# ice40_MotherBoard.net
KiCad netlist of a schematic drawn in Altium Designer
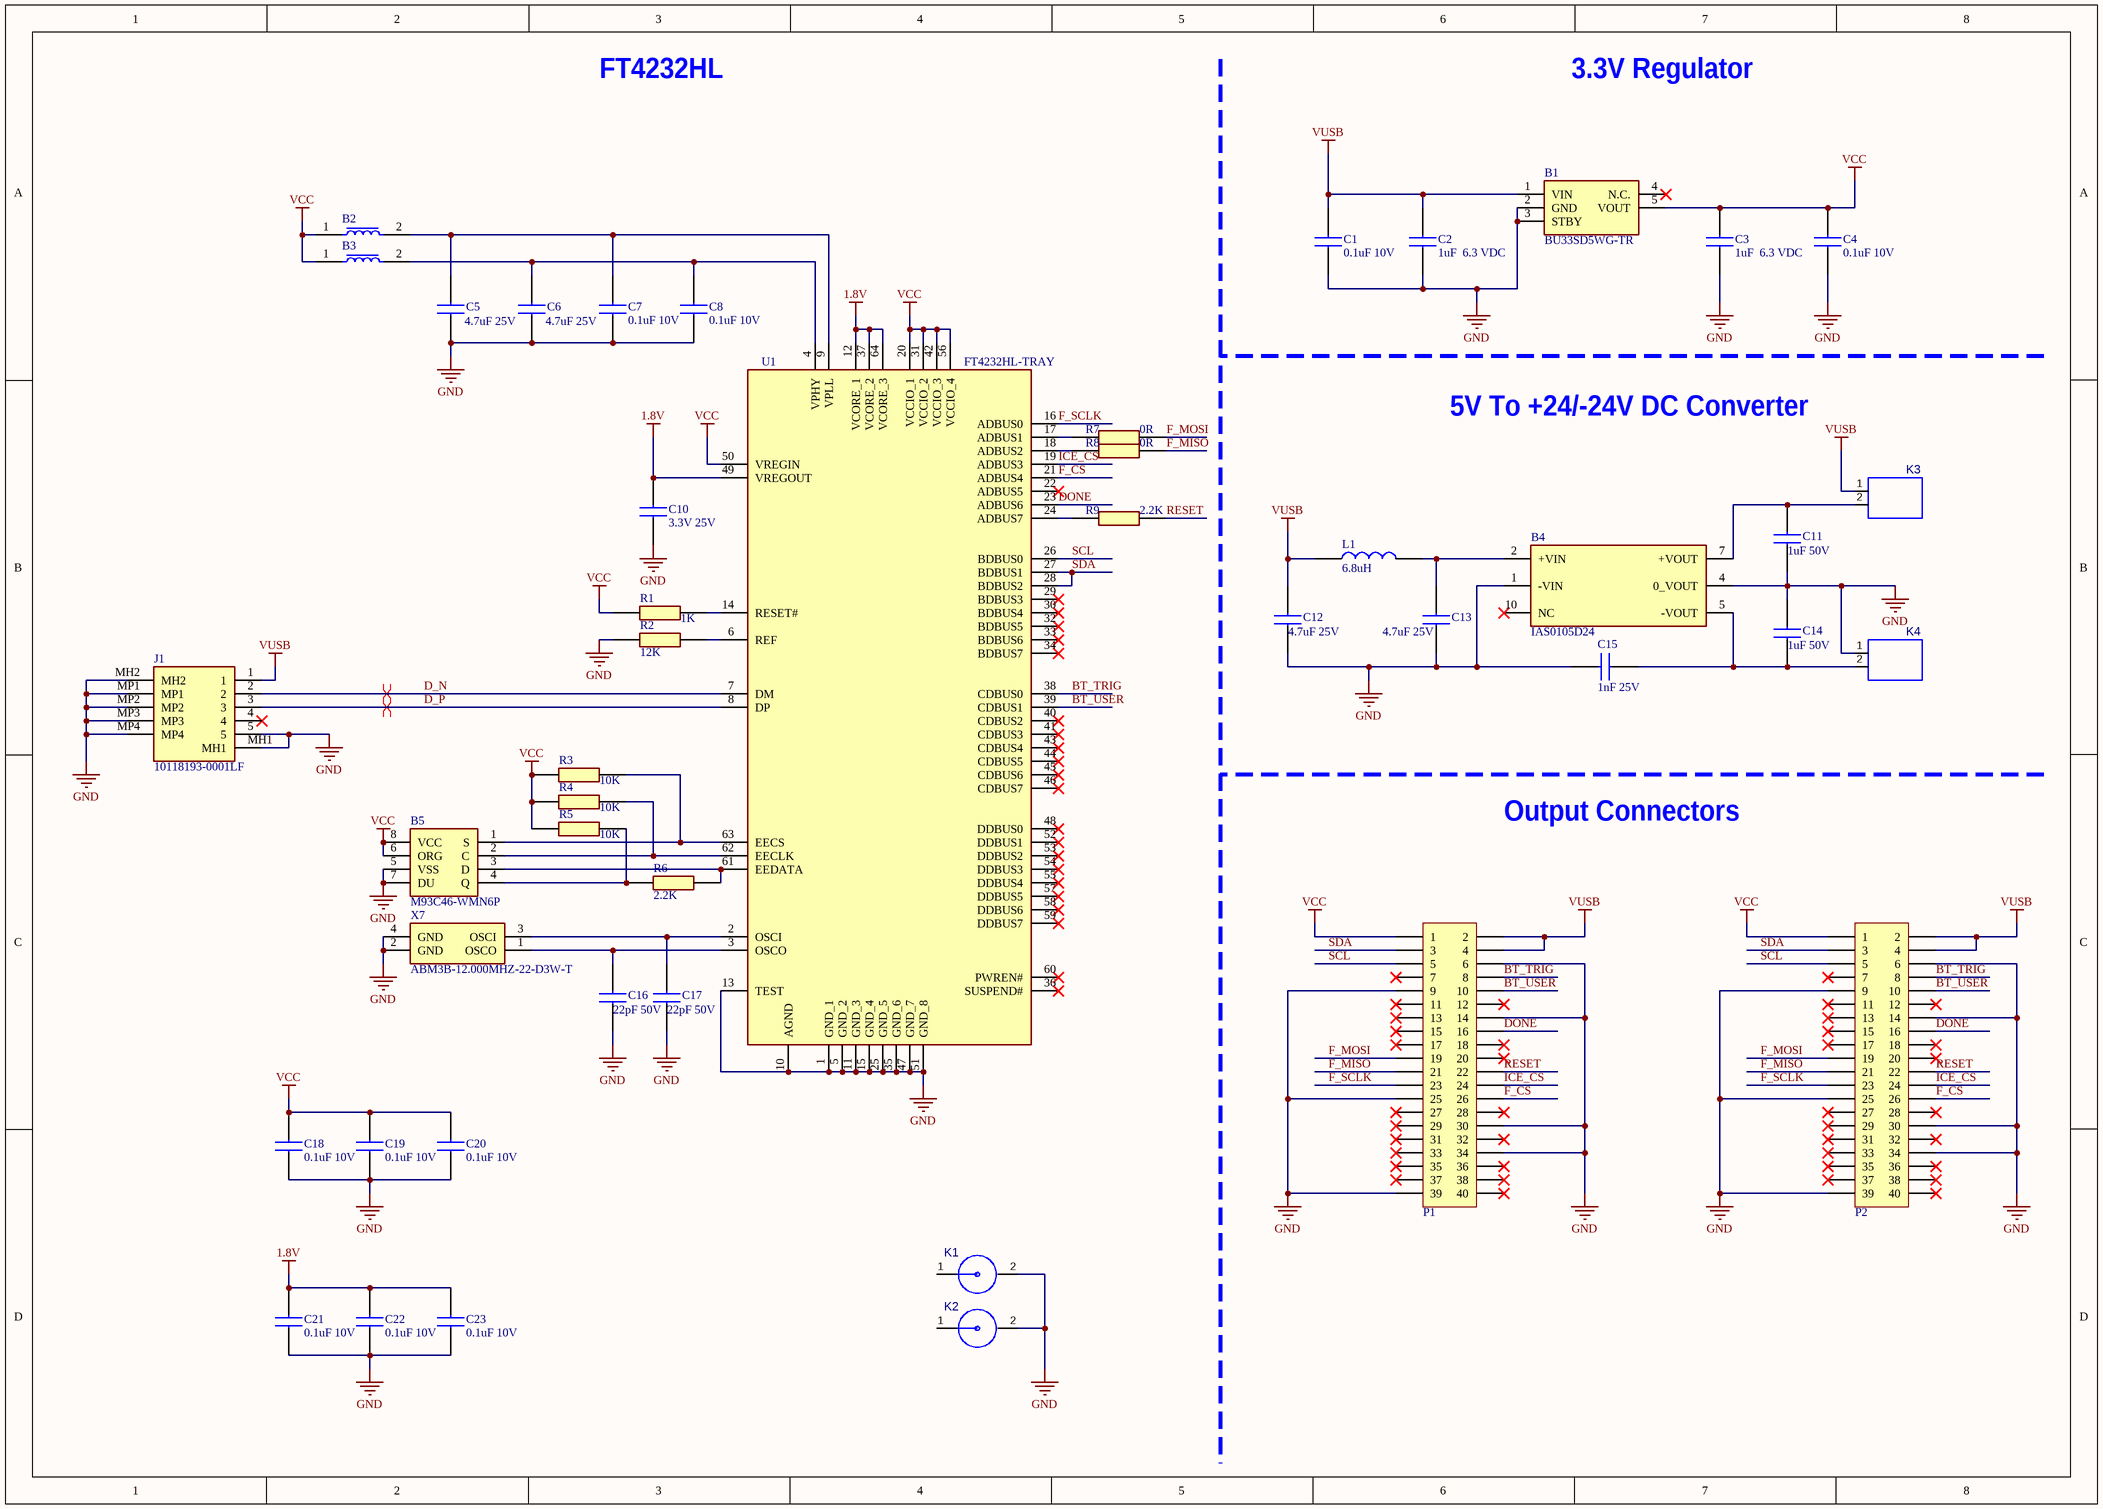
[diagram p0: ice40_MotherBoard.SchDoc]

(export (version "E")
  (design (tool "Eeschema 10.0.6"))
  (components
    (comp (ref "B1")
      (value "BU33SD5WG-TR")
      (footprint "SOT95P280X125-5N_")
      (fields (field (name "MOUSER PART NUMBER") "755-BU33SD5WG-TR"))
      (libsource (lib "BU33SD5WG-TR") (part "BU33SD5WG-TR"))
    )
    (comp (ref "B2")
      (value "BLM21AG102SN1D")
      (footprint "BLM21AG102BH1J")
      (description "BLM21_N1D Series EMI Suppression Filter 1000+/-25% at 100MHz 600mA @85")
      (fields (field (name "MOUSER PART NUMBER") "81-BLM21AG102SN1"))
      (libsource (lib "BLM21AG102SN1D") (part "BLM21AG102SN1D"))
    )
    (comp (ref "B3")
      (value "BLM21AG102SN1D")
      (footprint "BLM21AG102BH1J")
      (description "BLM21_N1D Series EMI Suppression Filter 1000+/-25% at 100MHz 600mA @85")
      (fields (field (name "MOUSER PART NUMBER") "81-BLM21AG102SN1"))
      (libsource (lib "BLM21AG102SN1D") (part "BLM21AG102SN1D"))
    )
    (comp (ref "B4")
      (value "IAS0105D24")
      (footprint "IAS0105D15_")
      (description "Isolated DC/DC Converters DC-DC, 1W, UNREGULATED, DUAL OUTPUT, SMD")
      (fields
        (field (name "MANUFACTURER_PART_NUMBER") "IAS0105D15")
        (field (name "MOUSER PART NUMBER") "209-IAS0105D15")
      )
      (libsource (lib "IAS0105D15") (part "IAS0105D15"))
    )
    (comp (ref "B5")
      (value "M93C46-WMN6P")
      (footprint "SOIC127P600X175-8N")
      (description "M93C46-WMN6P, Serial EEPROM Memory 1kbit, Serial-Microwire, 200ns 2.5  5.5 V, 8-Pin")
      (fields (field (name "MOUSER PART NUMBER") "511-M93C46-WMN6P"))
      (libsource (lib "M93C46-WMN6P") (part "M93C46-WMN6P"))
    )
    (comp (ref "C1")
      (value "0.1uF 10V")
      (footprint "C0805")
      (fields
        (field (name "MANUFACTURER_PART_NUMBER") "C0805C104K8RACAUTO")
        (field (name "MOUSER PART NUMBER") "80-C0805C104K8RAUTO")
      )
      (libsource (lib "C0805C104K8RACAUTO") (part "C0805C104K8RACAUTO"))
    )
    (comp (ref "C2")
      (value "1uF  6.3 VDC")
      (footprint "C0805")
      (fields
        (field (name "MANUFACTURER_PART_NUMBER") "C0805C105K9RACTU")
        (field (name "MOUSER PART NUMBER") "80-C0805C105K9R")
      )
      (libsource (lib "C0805C105K9RACTU") (part "C0805C105K9RACTU"))
    )
    (comp (ref "C3")
      (value "1uF  6.3 VDC")
      (footprint "C0805")
      (fields
        (field (name "MANUFACTURER_PART_NUMBER") "C0805C105K9RACTU")
        (field (name "MOUSER PART NUMBER") "80-C0805C105K9R")
      )
      (libsource (lib "C0805C105K9RACTU") (part "C0805C105K9RACTU"))
    )
    (comp (ref "C4")
      (value "0.1uF 10V")
      (footprint "C0805")
      (fields
        (field (name "MANUFACTURER_PART_NUMBER") "C0805C104K8RACAUTO")
        (field (name "MOUSER PART NUMBER") "80-C0805C104K8RAUTO")
      )
      (libsource (lib "C0805C104K8RACAUTO") (part "C0805C104K8RACAUTO"))
    )
    (comp (ref "C5")
      (value "4.7uF 25V")
      (footprint "C0805")
      (fields
        (field (name "MANUFACTURER_PART_NUMBER") "C0805C475K3RACTU")
        (field (name "MOUSER PART NUMBER") "80-C0805C475K3RACTU")
      )
      (libsource (lib "C0805C475K3RACTU") (part "C0805C475K3RACTU"))
    )
    (comp (ref "C6")
      (value "4.7uF 25V")
      (footprint "C0805")
      (fields
        (field (name "MANUFACTURER_PART_NUMBER") "C0805C475K3RACTU")
        (field (name "MOUSER PART NUMBER") "80-C0805C475K3RACTU")
      )
      (libsource (lib "C0805C475K3RACTU") (part "C0805C475K3RACTU"))
    )
    (comp (ref "C7")
      (value "0.1uF 10V")
      (footprint "C0805")
      (fields
        (field (name "MANUFACTURER_PART_NUMBER") "C0805C104K8RACAUTO")
        (field (name "MOUSER PART NUMBER") "80-C0805C104K8RAUTO")
      )
      (libsource (lib "C0805C104K8RACAUTO") (part "C0805C104K8RACAUTO"))
    )
    (comp (ref "C8")
      (value "0.1uF 10V")
      (footprint "C0805")
      (fields
        (field (name "MANUFACTURER_PART_NUMBER") "C0805C104K8RACAUTO")
        (field (name "MOUSER PART NUMBER") "80-C0805C104K8RAUTO")
      )
      (libsource (lib "C0805C104K8RACAUTO") (part "C0805C104K8RACAUTO"))
    )
    (comp (ref "C10")
      (value "3.3V 25V")
      (footprint "C0805")
      (description "TDK 0805 C 3.3uF Ceramic Multilayer Capacitor, 25 V dc, +125C, X7R Dielectric, +/-10%")
      (fields
        (field (name "MANUFACTURER_PART_NUMBER") "C2012X7R1E335K125AB")
        (field (name "MOUSER PART NUMBER") "810-C2012X7R1E335K")
      )
      (libsource (lib "C2012X7R1E335K125AB") (part "C2012X7R1E335K125AB"))
    )
    (comp (ref "C11")
      (value "1uF 50V")
      (footprint "C0805")
      (fields
        (field (name "MANUFACTURER_PART_NUMBER") "C0805C105K5RACTU")
        (field (name "MOUSER PART NUMBER") "80-C0805C105K5R")
      )
      (libsource (lib "C0805C105K5RACTU") (part "C0805C105K5RACTU"))
    )
    (comp (ref "C12")
      (value "4.7uF 25V")
      (footprint "C0805")
      (fields
        (field (name "MANUFACTURER_PART_NUMBER") "C0805C475K3RACTU")
        (field (name "MOUSER PART NUMBER") "80-C0805C475K3RACTU")
      )
      (libsource (lib "C0805C475K3RACTU") (part "C0805C475K3RACTU"))
    )
    (comp (ref "C13")
      (value "4.7uF 25V")
      (footprint "C0805")
      (fields
        (field (name "MANUFACTURER_PART_NUMBER") "C0805C475K3RACTU")
        (field (name "MOUSER PART NUMBER") "80-C0805C475K3RACTU")
      )
      (libsource (lib "C0805C475K3RACTU") (part "C0805C475K3RACTU"))
    )
    (comp (ref "C14")
      (value "1uF 50V")
      (footprint "C0805")
      (fields
        (field (name "MANUFACTURER_PART_NUMBER") "C0805C105K5RACTU")
        (field (name "MOUSER PART NUMBER") "80-C0805C105K5R")
      )
      (libsource (lib "C0805C105K5RACTU") (part "C0805C105K5RACTU"))
    )
    (comp (ref "C15")
      (value "1nF 25V")
      (footprint "C0805")
      (fields
        (field (name "MANUFACTURER_PART_NUMBER") "C0805C102K8RACTU")
        (field (name "MOUSER PART NUMBER") "80-C0805C102K8R")
      )
      (libsource (lib "C0805C102K8RACTU") (part "C0805C102K8RACTU"))
    )
    (comp (ref "C16")
      (value "22pF 50V")
      (footprint "C0805")
      (fields
        (field (name "MANUFACTURER_PART_NUMBER") "C0805C220F5GACTU")
        (field (name "MOUSER PART NUMBER") "80-C0805C220F5G")
      )
      (libsource (lib "C0805C220F5GACTU") (part "C0805C220F5GACTU"))
    )
    (comp (ref "C17")
      (value "22pF 50V")
      (footprint "C0805")
      (fields
        (field (name "MANUFACTURER_PART_NUMBER") "C0805C220F5GACTU")
        (field (name "MOUSER PART NUMBER") "80-C0805C220F5G")
      )
      (libsource (lib "C0805C220F5GACTU") (part "C0805C220F5GACTU"))
    )
    (comp (ref "C18")
      (value "0.1uF 10V")
      (footprint "C0805")
      (fields
        (field (name "MANUFACTURER_PART_NUMBER") "C0805C104K8RACAUTO")
        (field (name "MOUSER PART NUMBER") "80-C0805C104K8RAUTO")
      )
      (libsource (lib "C0805C104K8RACAUTO") (part "C0805C104K8RACAUTO"))
    )
    (comp (ref "C19")
      (value "0.1uF 10V")
      (footprint "C0805")
      (fields
        (field (name "MANUFACTURER_PART_NUMBER") "C0805C104K8RACAUTO")
        (field (name "MOUSER PART NUMBER") "80-C0805C104K8RAUTO")
      )
      (libsource (lib "C0805C104K8RACAUTO") (part "C0805C104K8RACAUTO"))
    )
    (comp (ref "C20")
      (value "0.1uF 10V")
      (footprint "C0805")
      (fields
        (field (name "MANUFACTURER_PART_NUMBER") "C0805C104K8RACAUTO")
        (field (name "MOUSER PART NUMBER") "80-C0805C104K8RAUTO")
      )
      (libsource (lib "C0805C104K8RACAUTO") (part "C0805C104K8RACAUTO"))
    )
    (comp (ref "C21")
      (value "0.1uF 10V")
      (footprint "C0805")
      (fields
        (field (name "MANUFACTURER_PART_NUMBER") "C0805C104K8RACAUTO")
        (field (name "MOUSER PART NUMBER") "80-C0805C104K8RAUTO")
      )
      (libsource (lib "C0805C104K8RACAUTO") (part "C0805C104K8RACAUTO"))
    )
    (comp (ref "C22")
      (value "0.1uF 10V")
      (footprint "C0805")
      (fields
        (field (name "MANUFACTURER_PART_NUMBER") "C0805C104K8RACAUTO")
        (field (name "MOUSER PART NUMBER") "80-C0805C104K8RAUTO")
      )
      (libsource (lib "C0805C104K8RACAUTO") (part "C0805C104K8RACAUTO"))
    )
    (comp (ref "C23")
      (value "0.1uF 10V")
      (footprint "C0805")
      (fields
        (field (name "MANUFACTURER_PART_NUMBER") "C0805C104K8RACAUTO")
        (field (name "MOUSER PART NUMBER") "80-C0805C104K8RAUTO")
      )
      (libsource (lib "C0805C104K8RACAUTO") (part "C0805C104K8RACAUTO"))
    )
    (comp (ref "J1")
      (value "10118193-0001LF")
      (footprint "shunt_resistor:101181930001LF")
      (description "Connector")
      (fields (field (name "MOUSER PART NUMBER") "649-10118193-0001LF"))
      (libsource (lib "*") (part "10118193-0001LF"))
    )
    (comp (ref "K1")
      (value "SMA_Edge")
      (footprint "AMPHENOL_132357-11_")
      (libsource (lib "alt_vovan") (part "SMA_Edge"))
    )
    (comp (ref "K2")
      (value "SMA_Edge")
      (footprint "AMPHENOL_132357-11_")
      (libsource (lib "alt_vovan") (part "SMA_Edge"))
    )
    (comp (ref "K3") (value "1x2PLS") (footprint "55342061_") (libsource (lib "alt2017") (part "1x2PLS")))
    (comp (ref "K4") (value "1x2PLS") (footprint "55342061_") (libsource (lib "alt2017") (part "1x2PLS")))
    (comp (ref "L1")
      (value "6.8uH")
      (footprint "INDC2012X110N_")
      (description "Fixed Inductors 0805 6.8uH 600mA DCR=420mOhms RF")
      (fields
        (field (name "MANUFACTURER_PART_NUMBER") "PE-0805CLH6R8STS")
        (field (name "MOUSER PART NUMBER") "673-PE-0805CLH6R8STS")
      )
      (libsource (lib "INDC2012X110N") (part "PE-0805CLH6R8STS"))
    )
    (comp (ref "P1")
      (value "2x20 2.54mm vertical")
      (footprint "RHDR40W97P254X254_2X20_5130X508X860P_")
      (description "SSQ-110-02-G-D-RA")
      (fields (field (name "PUBLISHER") "Altium Limited"))
      (libsource (lib "alt2017") (part "2x20 2.54mm vertical"))
    )
    (comp (ref "P2")
      (value "2x20 2.54mm vertical")
      (footprint "RHDR40W97P254X254_2X20_5130X508X860P_")
      (description "SSQ-110-02-G-D-RA")
      (fields (field (name "PUBLISHER") "Altium Limited"))
      (libsource (lib "alt2017") (part "2x20 2.54mm vertical"))
    )
    (comp (ref "R1")
      (value "1K")
      (footprint "6-0805_M")
      (description "RESISTOR, 0805 1K Ohm +/-5% 0.125 W")
      (fields
        (field (name "MANUFACTURER_PART_NUMBER") "ERJ-6GEYJ102V")
        (field (name "MOUSER PART NUMBER") "667-ERJ-6GEYJ102V")
      )
      (libsource (lib "ERJ-6GEYJ102V") (part "ERJ-6GEYJ102V"))
    )
    (comp (ref "R2")
      (value "12K")
      (footprint "6-0805_M")
      (description "Thick Film Resistors - SMD 0805 12Kohms 0.5W 1% AEC-Q200")
      (fields
        (field (name "MANUFACTURER_PART_NUMBER") "ERJ-P06F1202V")
        (field (name "MOUSER PART NUMBER") "667-ERJ-P06F1202V")
      )
      (libsource (lib "ERJ-P06F1202V") (part "ERJ-P06F1202V"))
    )
    (comp (ref "R3")
      (value "10K")
      (footprint "6-0805_M")
      (description "Resistor - SMD 10 kOhms 0805")
      (fields
        (field (name "MANUFACTURER_PART_NUMBER") "RC0805DR-072K2L")
        (field (name "MOUSER PART NUMBER") "603-RC0805DR-072K2L")
      )
      (libsource (lib "RC0805DR-072K2L") (part "RC0805DR-072K2L"))
    )
    (comp (ref "R4")
      (value "10K")
      (footprint "6-0805_M")
      (description "Resistor - SMD 10 kOhms 0805")
      (fields
        (field (name "MANUFACTURER_PART_NUMBER") "RC0805DR-072K2L")
        (field (name "MOUSER PART NUMBER") "603-RC0805DR-072K2L")
      )
      (libsource (lib "") (part "RC0805DR-072K2L_1"))
    )
    (comp (ref "R5")
      (value "10K")
      (footprint "6-0805_M")
      (description "Resistor - SMD 10 kOhms 0805")
      (fields
        (field (name "MANUFACTURER_PART_NUMBER") "RC0805DR-072K2L")
        (field (name "MOUSER PART NUMBER") "603-RC0805DR-072K2L")
      )
      (libsource (lib "") (part "RC0805DR-072K2L_1"))
    )
    (comp (ref "R6")
      (value "2.2K")
      (footprint "6-0805_M")
      (description "Thick Film Resistors - SMD 2.2 kOhms 125 mW 0805 1%")
      (fields
        (field (name "MANUFACTURER_PART_NUMBER") "ERJ-P06F1202V")
        (field (name "MOUSER PART NUMBER") "667-ERJ-P06F1202V")
      )
      (libsource (lib "ERJ-P06F1202V") (part "ERJ-P06F1202V"))
    )
    (comp (ref "R7")
      (value "0R")
      (footprint "0603-R")
      (description "RESISTOR, 0805 0R")
      (fields
        (field (name "MANUFACTURER_PART_NUMBER") "ERJ-6GEYJ102V")
        (field (name "MOUSER PART NUMBER") "667-ERJ-6GEYJ102V")
      )
      (libsource (lib "ERJ-6GEYJ102V") (part "ERJ-6GEYJ102V"))
    )
    (comp (ref "R8")
      (value "0R")
      (footprint "0603-R")
      (description "RESISTOR, 0805 0R")
      (fields
        (field (name "MANUFACTURER_PART_NUMBER") "ERJ-6GEYJ102V")
        (field (name "MOUSER PART NUMBER") "667-ERJ-6GEYJ102V")
      )
      (libsource (lib "ERJ-6GEYJ102V") (part "ERJ-6GEYJ102V"))
    )
    (comp (ref "R9")
      (value "2.2K")
      (footprint "6-0805_M")
      (description "Thick Film Resistors - SMD 2.2 kOhms 125 mW 0805 1%")
      (fields
        (field (name "MANUFACTURER_PART_NUMBER") "ERJ-P06F1202V")
        (field (name "MOUSER PART NUMBER") "667-ERJ-P06F1202V")
      )
      (libsource (lib "ERJ-P06F1202V") (part "ERJ-P06F1202V"))
    )
    (comp (ref "U1")
      (value "FT4232HL-TRAY")
      (footprint "QFP50P1200X1200X160-64N")
      (description "IC USB HS QUAD UART/SYNC 64-LQFP")
      (fields (field (name "MOUSER PART NUMBER") "895-FT4232HL-TRAY"))
      (libsource (lib "FT4232HL-TRAY") (part "FT4232HL-TRAY"))
    )
    (comp (ref "X7")
      (value "ABM3B-12.000MHZ-22-D3W-T")
      (footprint "ABM3B")
      (description "Crystals 12MHz 22pF 25ppm -40C +85C")
      (fields (field (name "MOUSER PART NUMBER") "815-ABM3B-12-22-D3WT"))
      (libsource (lib "ABM3B-12.000MHZ-22-D3W-T") (part "ABM3B-12.000MHZ-22-D3W-T"))
    )
  )
  (nets
    (net (code "1") (name "/BT_TRIG") (class "Default")
      (node (ref "P1") (pin "8") (pinfunction "8_8") (pintype "passive"))
      (node (ref "P2") (pin "8") (pinfunction "8_8") (pintype "passive"))
      (node (ref "U1") (pin "38") (pinfunction "CDBUS0_38") (pintype "passive"))
    )
    (net (code "2") (name "/BT_USER") (class "Default")
      (node (ref "P1") (pin "10") (pinfunction "10_10") (pintype "passive"))
      (node (ref "P2") (pin "10") (pinfunction "10_10") (pintype "passive"))
      (node (ref "U1") (pin "39") (pinfunction "CDBUS1_39") (pintype "passive"))
    )
    (net (code "3") (name "/DONE") (class "Default")
      (node (ref "P1") (pin "16") (pinfunction "16_16") (pintype "passive"))
      (node (ref "P2") (pin "16") (pinfunction "16_16") (pintype "passive"))
      (node (ref "U1") (pin "23") (pinfunction "ADBUS6_23") (pintype "passive"))
    )
    (net (code "4") (name "/D_N") (class "Default")
      (node (ref "J1") (pin "2") (pinfunction "2_2") (pintype "passive"))
      (node (ref "U1") (pin "7") (pinfunction "DM_7") (pintype "passive"))
    )
    (net (code "5") (name "/D_P") (class "Default")
      (node (ref "J1") (pin "3") (pinfunction "3_3") (pintype "passive"))
      (node (ref "U1") (pin "8") (pinfunction "DP_8") (pintype "passive"))
    )
    (net (code "6") (name "/F_CS") (class "Default")
      (node (ref "P1") (pin "26") (pinfunction "26_26") (pintype "passive"))
      (node (ref "P2") (pin "26") (pinfunction "26_26") (pintype "passive"))
      (node (ref "U1") (pin "21") (pinfunction "ADBUS4_21") (pintype "passive"))
    )
    (net (code "7") (name "/F_MISO") (class "Default")
      (node (ref "P1") (pin "21") (pinfunction "21_21") (pintype "passive"))
      (node (ref "P2") (pin "21") (pinfunction "21_21") (pintype "passive"))
      (node (ref "R8") (pin "2") (pinfunction "R2_2") (pintype "passive"))
    )
    (net (code "8") (name "/F_MOSI") (class "Default")
      (node (ref "P1") (pin "19") (pinfunction "19_19") (pintype "passive"))
      (node (ref "P2") (pin "19") (pinfunction "19_19") (pintype "passive"))
      (node (ref "R7") (pin "2") (pinfunction "R2_2") (pintype "passive"))
    )
    (net (code "9") (name "/F_SCLK") (class "Default")
      (node (ref "P1") (pin "23") (pinfunction "23_23") (pintype "passive"))
      (node (ref "P2") (pin "23") (pinfunction "23_23") (pintype "passive"))
      (node (ref "U1") (pin "16") (pinfunction "ADBUS0_16") (pintype "passive"))
    )
    (net (code "10") (name "/ICE_CS") (class "Default")
      (node (ref "P1") (pin "24") (pinfunction "24_24") (pintype "passive"))
      (node (ref "P2") (pin "24") (pinfunction "24_24") (pintype "passive"))
      (node (ref "U1") (pin "19") (pinfunction "ADBUS3_19") (pintype "passive"))
    )
    (net (code "11") (name "/RESET") (class "Default")
      (node (ref "P1") (pin "22") (pinfunction "22_22") (pintype "passive"))
      (node (ref "P2") (pin "22") (pinfunction "22_22") (pintype "passive"))
      (node (ref "R9") (pin "2") (pinfunction "2_2") (pintype "passive"))
    )
    (net (code "12") (name "/SCL") (class "Default")
      (node (ref "P1") (pin "5") (pinfunction "5_5") (pintype "passive"))
      (node (ref "P2") (pin "5") (pinfunction "5_5") (pintype "passive"))
      (node (ref "U1") (pin "26") (pinfunction "BDBUS0_26") (pintype "passive"))
    )
    (net (code "13") (name "/SDA") (class "Default")
      (node (ref "P1") (pin "3") (pinfunction "3_3") (pintype "passive"))
      (node (ref "P2") (pin "3") (pinfunction "3_3") (pintype "passive"))
      (node (ref "U1") (pin "27") (pinfunction "BDBUS1_27") (pintype "passive"))
      (node (ref "U1") (pin "28") (pinfunction "BDBUS2_28") (pintype "passive"))
    )
    (net (code "14") (name "1.8V") (class "Default")
      (node (ref "C10") (pin "2") (pinfunction "2_2") (pintype "passive"))
      (node (ref "C21") (pin "2") (pinfunction "2_2") (pintype "passive"))
      (node (ref "C22") (pin "2") (pinfunction "2_2") (pintype "passive"))
      (node (ref "C23") (pin "2") (pinfunction "2_2") (pintype "passive"))
      (node (ref "U1") (pin "12") (pinfunction "VCORE_1_12") (pintype "passive"))
      (node (ref "U1") (pin "37") (pinfunction "VCORE_2_37") (pintype "passive"))
      (node (ref "U1") (pin "49") (pinfunction "VREGOUT_49") (pintype "passive"))
      (node (ref "U1") (pin "64") (pinfunction "VCORE_3_64") (pintype "passive"))
    )
    (net (code "15") (name "GND") (class "Default")
      (node (ref "B1") (pin "2") (pinfunction "GND_2") (pintype "passive"))
      (node (ref "B1") (pin "3") (pinfunction "STBY_3") (pintype "passive"))
      (node (ref "B4") (pin "1") (pinfunction "-VIN_1") (pintype "passive"))
      (node (ref "B4") (pin "4") (pinfunction "0_VOUT_4") (pintype "passive"))
      (node (ref "B5") (pin "5") (pinfunction "VSS_5") (pintype "power_in"))
      (node (ref "B5") (pin "7") (pinfunction "DU_7") (pintype "passive"))
      (node (ref "C1") (pin "1") (pinfunction "1_1") (pintype "passive"))
      (node (ref "C10") (pin "1") (pinfunction "1_1") (pintype "passive"))
      (node (ref "C11") (pin "1") (pinfunction "1_1") (pintype "passive"))
      (node (ref "C12") (pin "1") (pinfunction "1_1") (pintype "passive"))
      (node (ref "C13") (pin "1") (pinfunction "1_1") (pintype "passive"))
      (node (ref "C14") (pin "2") (pinfunction "2_2") (pintype "passive"))
      (node (ref "C15") (pin "1") (pinfunction "1_1") (pintype "passive"))
      (node (ref "C16") (pin "1") (pinfunction "1_1") (pintype "passive"))
      (node (ref "C17") (pin "1") (pinfunction "1_1") (pintype "passive"))
      (node (ref "C18") (pin "1") (pinfunction "1_1") (pintype "passive"))
      (node (ref "C19") (pin "1") (pinfunction "1_1") (pintype "passive"))
      (node (ref "C2") (pin "1") (pinfunction "1_1") (pintype "passive"))
      (node (ref "C20") (pin "1") (pinfunction "1_1") (pintype "passive"))
      (node (ref "C21") (pin "1") (pinfunction "1_1") (pintype "passive"))
      (node (ref "C22") (pin "1") (pinfunction "1_1") (pintype "passive"))
      (node (ref "C23") (pin "1") (pinfunction "1_1") (pintype "passive"))
      (node (ref "C3") (pin "1") (pinfunction "1_1") (pintype "passive"))
      (node (ref "C4") (pin "1") (pinfunction "1_1") (pintype "passive"))
      (node (ref "C5") (pin "1") (pinfunction "1_1") (pintype "passive"))
      (node (ref "C6") (pin "1") (pinfunction "1_1") (pintype "passive"))
      (node (ref "C7") (pin "1") (pinfunction "1_1") (pintype "passive"))
      (node (ref "C8") (pin "1") (pinfunction "1_1") (pintype "passive"))
      (node (ref "J1") (pin "5") (pinfunction "5_5") (pintype "passive"))
      (node (ref "J1") (pin "MH1") (pinfunction "MH1_MH1") (pintype "passive"))
      (node (ref "J1") (pin "MH2") (pinfunction "MH2_MH2") (pintype "passive"))
      (node (ref "J1") (pin "MP1") (pinfunction "MP1_MP1") (pintype "passive"))
      (node (ref "J1") (pin "MP2") (pinfunction "MP2_MP2") (pintype "passive"))
      (node (ref "J1") (pin "MP3") (pinfunction "MP3_MP3") (pintype "passive"))
      (node (ref "J1") (pin "MP4") (pinfunction "MP4_MP4") (pintype "passive"))
      (node (ref "K1") (pin "2") (pinfunction "2_2") (pintype "passive"))
      (node (ref "K2") (pin "2") (pinfunction "2_2") (pintype "passive"))
      (node (ref "K4") (pin "1") (pinfunction "1_1") (pintype "passive"))
      (node (ref "P1") (pin "14") (pinfunction "14_14") (pintype "passive"))
      (node (ref "P1") (pin "25") (pinfunction "25_25") (pintype "passive"))
      (node (ref "P1") (pin "30") (pinfunction "30_30") (pintype "passive"))
      (node (ref "P1") (pin "34") (pinfunction "34_34") (pintype "passive"))
      (node (ref "P1") (pin "39") (pinfunction "39_39") (pintype "passive"))
      (node (ref "P1") (pin "6") (pinfunction "6_6") (pintype "passive"))
      (node (ref "P1") (pin "9") (pinfunction "9_9") (pintype "passive"))
      (node (ref "P2") (pin "14") (pinfunction "14_14") (pintype "passive"))
      (node (ref "P2") (pin "25") (pinfunction "25_25") (pintype "passive"))
      (node (ref "P2") (pin "30") (pinfunction "30_30") (pintype "passive"))
      (node (ref "P2") (pin "34") (pinfunction "34_34") (pintype "passive"))
      (node (ref "P2") (pin "39") (pinfunction "39_39") (pintype "passive"))
      (node (ref "P2") (pin "6") (pinfunction "6_6") (pintype "passive"))
      (node (ref "P2") (pin "9") (pinfunction "9_9") (pintype "passive"))
      (node (ref "R2") (pin "1") (pinfunction "1_1") (pintype "passive"))
      (node (ref "U1") (pin "1") (pinfunction "GND_1_1") (pintype "passive"))
      (node (ref "U1") (pin "10") (pinfunction "AGND_10") (pintype "passive"))
      (node (ref "U1") (pin "11") (pinfunction "GND_3_11") (pintype "passive"))
      (node (ref "U1") (pin "13") (pinfunction "TEST_13") (pintype "passive"))
      (node (ref "U1") (pin "15") (pinfunction "GND_4_15") (pintype "passive"))
      (node (ref "U1") (pin "25") (pinfunction "GND_5_25") (pintype "passive"))
      (node (ref "U1") (pin "35") (pinfunction "GND_6_35") (pintype "passive"))
      (node (ref "U1") (pin "47") (pinfunction "GND_7_47") (pintype "passive"))
      (node (ref "U1") (pin "5") (pinfunction "GND_2_5") (pintype "passive"))
      (node (ref "U1") (pin "51") (pinfunction "GND_8_51") (pintype "passive"))
      (node (ref "X7") (pin "2") (pinfunction "GND_2") (pintype "passive"))
      (node (ref "X7") (pin "4") (pinfunction "GND_4") (pintype "passive"))
    )
    (net (code "16") (name "Net-(B4-+VIN)") (class "Default")
      (node (ref "B4") (pin "2") (pinfunction "+VIN_2") (pintype "passive"))
      (node (ref "C13") (pin "2") (pinfunction "2_2") (pintype "passive"))
      (node (ref "L1") (pin "2") (pinfunction "2_2") (pintype "passive"))
    )
    (net (code "17") (name "Net-(B4-+VOUT)") (class "Default")
      (node (ref "B4") (pin "7") (pinfunction "+VOUT_7") (pintype "passive"))
      (node (ref "C11") (pin "2") (pinfunction "2_2") (pintype "passive"))
      (node (ref "K3") (pin "2") (pinfunction "2_2") (pintype "passive"))
    )
    (net (code "18") (name "Net-(B4--VOUT)") (class "Default")
      (node (ref "B4") (pin "5") (pinfunction "-VOUT_5") (pintype "passive"))
      (node (ref "C14") (pin "1") (pinfunction "1_1") (pintype "passive"))
      (node (ref "C15") (pin "2") (pinfunction "2_2") (pintype "passive"))
      (node (ref "K4") (pin "2") (pinfunction "2_2") (pintype "passive"))
    )
    (net (code "19") (name "Net-(B5-C)") (class "Default")
      (node (ref "B5") (pin "2") (pinfunction "C_2") (pintype "passive"))
      (node (ref "R4") (pin "2") (pinfunction "2_2") (pintype "passive"))
      (node (ref "U1") (pin "62") (pinfunction "EECLK_62") (pintype "passive"))
    )
    (net (code "20") (name "Net-(B5-D)") (class "Default")
      (node (ref "B5") (pin "3") (pinfunction "D_3") (pintype "passive"))
      (node (ref "R6") (pin "2") (pinfunction "2_2") (pintype "passive"))
      (node (ref "U1") (pin "61") (pinfunction "EEDATA_61") (pintype "passive"))
    )
    (net (code "21") (name "Net-(B5-Q)") (class "Default")
      (node (ref "B5") (pin "4") (pinfunction "Q_4") (pintype "passive"))
      (node (ref "R5") (pin "2") (pinfunction "2_2") (pintype "passive"))
      (node (ref "R6") (pin "1") (pinfunction "1_1") (pintype "passive"))
    )
    (net (code "22") (name "Net-(B5-S)") (class "Default")
      (node (ref "B5") (pin "1") (pinfunction "S_1") (pintype "passive"))
      (node (ref "R3") (pin "1") (pinfunction "1_1") (pintype "passive"))
      (node (ref "U1") (pin "63") (pinfunction "EECS_63") (pintype "passive"))
    )
    (net (code "23") (name "Net-(R1-R2)") (class "Default")
      (node (ref "R1") (pin "2") (pinfunction "R2_2") (pintype "passive"))
      (node (ref "U1") (pin "14") (pinfunction "RESET#_14") (pintype "passive"))
    )
    (net (code "24") (name "Net-(R7-R1)") (class "Default")
      (node (ref "R7") (pin "1") (pinfunction "R1_1") (pintype "passive"))
      (node (ref "U1") (pin "17") (pinfunction "ADBUS1_17") (pintype "passive"))
    )
    (net (code "25") (name "Net-(R8-R1)") (class "Default")
      (node (ref "R8") (pin "1") (pinfunction "R1_1") (pintype "passive"))
      (node (ref "U1") (pin "18") (pinfunction "ADBUS2_18") (pintype "passive"))
    )
    (net (code "26") (name "Net-(U1-ADBUS7)") (class "Default")
      (node (ref "R9") (pin "1") (pinfunction "1_1") (pintype "passive"))
      (node (ref "U1") (pin "24") (pinfunction "ADBUS7_24") (pintype "passive"))
    )
    (net (code "27") (name "Net-(U1-OSCI)") (class "Default")
      (node (ref "C17") (pin "2") (pinfunction "2_2") (pintype "passive"))
      (node (ref "U1") (pin "2") (pinfunction "OSCI_2") (pintype "passive"))
      (node (ref "X7") (pin "3") (pinfunction "OSCI_3") (pintype "passive"))
    )
    (net (code "28") (name "Net-(U1-OSCO)") (class "Default")
      (node (ref "C16") (pin "2") (pinfunction "2_2") (pintype "passive"))
      (node (ref "U1") (pin "3") (pinfunction "OSCO_3") (pintype "passive"))
      (node (ref "X7") (pin "1") (pinfunction "OSCO_1") (pintype "passive"))
    )
    (net (code "29") (name "Net-(U1-REF)") (class "Default")
      (node (ref "R2") (pin "2") (pinfunction "2_2") (pintype "passive"))
      (node (ref "U1") (pin "6") (pinfunction "REF_6") (pintype "passive"))
    )
    (net (code "30") (name "Net-(U1-VPHY)") (class "Default")
      (node (ref "B3") (pin "2") (pinfunction "2_2") (pintype "passive"))
      (node (ref "C6") (pin "2") (pinfunction "2_2") (pintype "passive"))
      (node (ref "C8") (pin "2") (pinfunction "2_2") (pintype "passive"))
      (node (ref "U1") (pin "4") (pinfunction "VPHY_4") (pintype "passive"))
    )
    (net (code "31") (name "Net-(U1-VPLL)") (class "Default")
      (node (ref "B2") (pin "2") (pinfunction "2_2") (pintype "passive"))
      (node (ref "C5") (pin "2") (pinfunction "2_2") (pintype "passive"))
      (node (ref "C7") (pin "2") (pinfunction "2_2") (pintype "passive"))
      (node (ref "U1") (pin "9") (pinfunction "VPLL_9") (pintype "passive"))
    )
    (net (code "32") (name "VCC") (class "Default")
      (node (ref "B1") (pin "5") (pinfunction "VOUT_5") (pintype "passive"))
      (node (ref "B2") (pin "1") (pinfunction "1_1") (pintype "passive"))
      (node (ref "B3") (pin "1") (pinfunction "1_1") (pintype "passive"))
      (node (ref "B5") (pin "6") (pinfunction "ORG_6") (pintype "passive"))
      (node (ref "B5") (pin "8") (pinfunction "VCC_8") (pintype "power_in"))
      (node (ref "C18") (pin "2") (pinfunction "2_2") (pintype "passive"))
      (node (ref "C19") (pin "2") (pinfunction "2_2") (pintype "passive"))
      (node (ref "C20") (pin "2") (pinfunction "2_2") (pintype "passive"))
      (node (ref "C3") (pin "2") (pinfunction "2_2") (pintype "passive"))
      (node (ref "C4") (pin "2") (pinfunction "2_2") (pintype "passive"))
      (node (ref "P1") (pin "1") (pinfunction "1_1") (pintype "passive"))
      (node (ref "P2") (pin "1") (pinfunction "1_1") (pintype "passive"))
      (node (ref "R1") (pin "1") (pinfunction "R1_1") (pintype "passive"))
      (node (ref "R3") (pin "2") (pinfunction "2_2") (pintype "passive"))
      (node (ref "R4") (pin "1") (pinfunction "1_1") (pintype "passive"))
      (node (ref "R5") (pin "1") (pinfunction "1_1") (pintype "passive"))
      (node (ref "U1") (pin "20") (pinfunction "VCCIO_1_20") (pintype "passive"))
      (node (ref "U1") (pin "31") (pinfunction "VCCIO_2_31") (pintype "passive"))
      (node (ref "U1") (pin "42") (pinfunction "VCCIO_3_42") (pintype "passive"))
      (node (ref "U1") (pin "50") (pinfunction "VREGIN_50") (pintype "passive"))
      (node (ref "U1") (pin "56") (pinfunction "VCCIO_4_56") (pintype "passive"))
    )
    (net (code "33") (name "VUSB") (class "Default")
      (node (ref "B1") (pin "1") (pinfunction "VIN_1") (pintype "passive"))
      (node (ref "C1") (pin "2") (pinfunction "2_2") (pintype "passive"))
      (node (ref "C12") (pin "2") (pinfunction "2_2") (pintype "passive"))
      (node (ref "C2") (pin "2") (pinfunction "2_2") (pintype "passive"))
      (node (ref "J1") (pin "1") (pinfunction "1_1") (pintype "passive"))
      (node (ref "K3") (pin "1") (pinfunction "1_1") (pintype "passive"))
      (node (ref "L1") (pin "1") (pinfunction "1_1") (pintype "passive"))
      (node (ref "P1") (pin "2") (pinfunction "2_2") (pintype "passive"))
      (node (ref "P1") (pin "4") (pinfunction "4_4") (pintype "passive"))
      (node (ref "P2") (pin "2") (pinfunction "2_2") (pintype "passive"))
      (node (ref "P2") (pin "4") (pinfunction "4_4") (pintype "passive"))
    )
    (net (code "34") (name "unconnected-(B1-N.C.-Pad4)") (class "Default")
      (node (ref "B1") (pin "4") (pinfunction "N.C._4") (pintype "passive+no_connect"))
    )
    (net (code "35") (name "unconnected-(B4-NC-Pad10)") (class "Default")
      (node (ref "B4") (pin "10") (pinfunction "NC_10") (pintype "passive+no_connect"))
    )
    (net (code "36") (name "unconnected-(J1-Pad4)") (class "Default")
      (node (ref "J1") (pin "4") (pinfunction "4_4") (pintype "passive+no_connect"))
    )
    (net (code "37") (name "unconnected-(K1-Pad1)") (class "Default")
      (node (ref "K1") (pin "1") (pinfunction "1_1") (pintype "passive"))
    )
    (net (code "38") (name "unconnected-(K2-Pad1)") (class "Default")
      (node (ref "K2") (pin "1") (pinfunction "1_1") (pintype "passive"))
    )
    (net (code "39") (name "unconnected-(P1-Pad7)") (class "Default")
      (node (ref "P1") (pin "7") (pinfunction "7_7") (pintype "passive+no_connect"))
    )
    (net (code "40") (name "unconnected-(P1-Pad11)") (class "Default")
      (node (ref "P1") (pin "11") (pinfunction "11_11") (pintype "passive+no_connect"))
    )
    (net (code "41") (name "unconnected-(P1-Pad12)") (class "Default")
      (node (ref "P1") (pin "12") (pinfunction "12_12") (pintype "passive+no_connect"))
    )
    (net (code "42") (name "unconnected-(P1-Pad13)") (class "Default")
      (node (ref "P1") (pin "13") (pinfunction "13_13") (pintype "passive+no_connect"))
    )
    (net (code "43") (name "unconnected-(P1-Pad15)") (class "Default")
      (node (ref "P1") (pin "15") (pinfunction "15_15") (pintype "passive+no_connect"))
    )
    (net (code "44") (name "unconnected-(P1-Pad17)") (class "Default")
      (node (ref "P1") (pin "17") (pinfunction "17_17") (pintype "passive+no_connect"))
    )
    (net (code "45") (name "unconnected-(P1-Pad18)") (class "Default")
      (node (ref "P1") (pin "18") (pinfunction "18_18") (pintype "passive+no_connect"))
    )
    (net (code "46") (name "unconnected-(P1-Pad20)") (class "Default")
      (node (ref "P1") (pin "20") (pinfunction "20_20") (pintype "passive+no_connect"))
    )
    (net (code "47") (name "unconnected-(P1-Pad27)") (class "Default")
      (node (ref "P1") (pin "27") (pinfunction "27_27") (pintype "passive+no_connect"))
    )
    (net (code "48") (name "unconnected-(P1-Pad28)") (class "Default")
      (node (ref "P1") (pin "28") (pinfunction "28_28") (pintype "passive+no_connect"))
    )
    (net (code "49") (name "unconnected-(P1-Pad29)") (class "Default")
      (node (ref "P1") (pin "29") (pinfunction "29_29") (pintype "passive+no_connect"))
    )
    (net (code "50") (name "unconnected-(P1-Pad31)") (class "Default")
      (node (ref "P1") (pin "31") (pinfunction "31_31") (pintype "passive+no_connect"))
    )
    (net (code "51") (name "unconnected-(P1-Pad32)") (class "Default")
      (node (ref "P1") (pin "32") (pinfunction "32_32") (pintype "passive+no_connect"))
    )
    (net (code "52") (name "unconnected-(P1-Pad33)") (class "Default")
      (node (ref "P1") (pin "33") (pinfunction "33_33") (pintype "passive+no_connect"))
    )
    (net (code "53") (name "unconnected-(P1-Pad35)") (class "Default")
      (node (ref "P1") (pin "35") (pinfunction "35_35") (pintype "passive+no_connect"))
    )
    (net (code "54") (name "unconnected-(P1-Pad36)") (class "Default")
      (node (ref "P1") (pin "36") (pinfunction "36_36") (pintype "passive+no_connect"))
    )
    (net (code "55") (name "unconnected-(P1-Pad37)") (class "Default")
      (node (ref "P1") (pin "37") (pinfunction "37_37") (pintype "passive+no_connect"))
    )
    (net (code "56") (name "unconnected-(P1-Pad38)") (class "Default")
      (node (ref "P1") (pin "38") (pinfunction "38_38") (pintype "passive+no_connect"))
    )
    (net (code "57") (name "unconnected-(P1-Pad40)") (class "Default")
      (node (ref "P1") (pin "40") (pinfunction "40_40") (pintype "passive+no_connect"))
    )
    (net (code "58") (name "unconnected-(P2-Pad7)") (class "Default")
      (node (ref "P2") (pin "7") (pinfunction "7_7") (pintype "passive+no_connect"))
    )
    (net (code "59") (name "unconnected-(P2-Pad11)") (class "Default")
      (node (ref "P2") (pin "11") (pinfunction "11_11") (pintype "passive+no_connect"))
    )
    (net (code "60") (name "unconnected-(P2-Pad12)") (class "Default")
      (node (ref "P2") (pin "12") (pinfunction "12_12") (pintype "passive+no_connect"))
    )
    (net (code "61") (name "unconnected-(P2-Pad13)") (class "Default")
      (node (ref "P2") (pin "13") (pinfunction "13_13") (pintype "passive+no_connect"))
    )
    (net (code "62") (name "unconnected-(P2-Pad15)") (class "Default")
      (node (ref "P2") (pin "15") (pinfunction "15_15") (pintype "passive+no_connect"))
    )
    (net (code "63") (name "unconnected-(P2-Pad17)") (class "Default")
      (node (ref "P2") (pin "17") (pinfunction "17_17") (pintype "passive+no_connect"))
    )
    (net (code "64") (name "unconnected-(P2-Pad18)") (class "Default")
      (node (ref "P2") (pin "18") (pinfunction "18_18") (pintype "passive+no_connect"))
    )
    (net (code "65") (name "unconnected-(P2-Pad20)") (class "Default")
      (node (ref "P2") (pin "20") (pinfunction "20_20") (pintype "passive+no_connect"))
    )
    (net (code "66") (name "unconnected-(P2-Pad27)") (class "Default")
      (node (ref "P2") (pin "27") (pinfunction "27_27") (pintype "passive+no_connect"))
    )
    (net (code "67") (name "unconnected-(P2-Pad28)") (class "Default")
      (node (ref "P2") (pin "28") (pinfunction "28_28") (pintype "passive+no_connect"))
    )
    (net (code "68") (name "unconnected-(P2-Pad29)") (class "Default")
      (node (ref "P2") (pin "29") (pinfunction "29_29") (pintype "passive+no_connect"))
    )
    (net (code "69") (name "unconnected-(P2-Pad31)") (class "Default")
      (node (ref "P2") (pin "31") (pinfunction "31_31") (pintype "passive+no_connect"))
    )
    (net (code "70") (name "unconnected-(P2-Pad32)") (class "Default")
      (node (ref "P2") (pin "32") (pinfunction "32_32") (pintype "passive+no_connect"))
    )
    (net (code "71") (name "unconnected-(P2-Pad33)") (class "Default")
      (node (ref "P2") (pin "33") (pinfunction "33_33") (pintype "passive+no_connect"))
    )
    (net (code "72") (name "unconnected-(P2-Pad35)") (class "Default")
      (node (ref "P2") (pin "35") (pinfunction "35_35") (pintype "passive+no_connect"))
    )
    (net (code "73") (name "unconnected-(P2-Pad36)") (class "Default")
      (node (ref "P2") (pin "36") (pinfunction "36_36") (pintype "passive+no_connect"))
    )
    (net (code "74") (name "unconnected-(P2-Pad37)") (class "Default")
      (node (ref "P2") (pin "37") (pinfunction "37_37") (pintype "passive+no_connect"))
    )
    (net (code "75") (name "unconnected-(P2-Pad38)") (class "Default")
      (node (ref "P2") (pin "38") (pinfunction "38_38") (pintype "passive+no_connect"))
    )
    (net (code "76") (name "unconnected-(P2-Pad40)") (class "Default")
      (node (ref "P2") (pin "40") (pinfunction "40_40") (pintype "passive+no_connect"))
    )
    (net (code "77") (name "unconnected-(U1-ADBUS5-Pad22)") (class "Default")
      (node (ref "U1") (pin "22") (pinfunction "ADBUS5_22") (pintype "passive+no_connect"))
    )
    (net (code "78") (name "unconnected-(U1-BDBUS3-Pad29)") (class "Default")
      (node (ref "U1") (pin "29") (pinfunction "BDBUS3_29") (pintype "passive+no_connect"))
    )
    (net (code "79") (name "unconnected-(U1-BDBUS4-Pad30)") (class "Default")
      (node (ref "U1") (pin "30") (pinfunction "BDBUS4_30") (pintype "passive+no_connect"))
    )
    (net (code "80") (name "unconnected-(U1-BDBUS5-Pad32)") (class "Default")
      (node (ref "U1") (pin "32") (pinfunction "BDBUS5_32") (pintype "passive+no_connect"))
    )
    (net (code "81") (name "unconnected-(U1-BDBUS6-Pad33)") (class "Default")
      (node (ref "U1") (pin "33") (pinfunction "BDBUS6_33") (pintype "passive+no_connect"))
    )
    (net (code "82") (name "unconnected-(U1-BDBUS7-Pad34)") (class "Default")
      (node (ref "U1") (pin "34") (pinfunction "BDBUS7_34") (pintype "passive+no_connect"))
    )
    (net (code "83") (name "unconnected-(U1-CDBUS2-Pad40)") (class "Default")
      (node (ref "U1") (pin "40") (pinfunction "CDBUS2_40") (pintype "passive+no_connect"))
    )
    (net (code "84") (name "unconnected-(U1-CDBUS3-Pad41)") (class "Default")
      (node (ref "U1") (pin "41") (pinfunction "CDBUS3_41") (pintype "passive+no_connect"))
    )
    (net (code "85") (name "unconnected-(U1-CDBUS4-Pad43)") (class "Default")
      (node (ref "U1") (pin "43") (pinfunction "CDBUS4_43") (pintype "passive+no_connect"))
    )
    (net (code "86") (name "unconnected-(U1-CDBUS5-Pad44)") (class "Default")
      (node (ref "U1") (pin "44") (pinfunction "CDBUS5_44") (pintype "passive+no_connect"))
    )
    (net (code "87") (name "unconnected-(U1-CDBUS6-Pad45)") (class "Default")
      (node (ref "U1") (pin "45") (pinfunction "CDBUS6_45") (pintype "passive+no_connect"))
    )
    (net (code "88") (name "unconnected-(U1-CDBUS7-Pad46)") (class "Default")
      (node (ref "U1") (pin "46") (pinfunction "CDBUS7_46") (pintype "passive+no_connect"))
    )
    (net (code "89") (name "unconnected-(U1-DDBUS0-Pad48)") (class "Default")
      (node (ref "U1") (pin "48") (pinfunction "DDBUS0_48") (pintype "passive+no_connect"))
    )
    (net (code "90") (name "unconnected-(U1-DDBUS1-Pad52)") (class "Default")
      (node (ref "U1") (pin "52") (pinfunction "DDBUS1_52") (pintype "passive+no_connect"))
    )
    (net (code "91") (name "unconnected-(U1-DDBUS2-Pad53)") (class "Default")
      (node (ref "U1") (pin "53") (pinfunction "DDBUS2_53") (pintype "passive+no_connect"))
    )
    (net (code "92") (name "unconnected-(U1-DDBUS3-Pad54)") (class "Default")
      (node (ref "U1") (pin "54") (pinfunction "DDBUS3_54") (pintype "passive+no_connect"))
    )
    (net (code "93") (name "unconnected-(U1-DDBUS4-Pad55)") (class "Default")
      (node (ref "U1") (pin "55") (pinfunction "DDBUS4_55") (pintype "passive+no_connect"))
    )
    (net (code "94") (name "unconnected-(U1-DDBUS5-Pad57)") (class "Default")
      (node (ref "U1") (pin "57") (pinfunction "DDBUS5_57") (pintype "passive+no_connect"))
    )
    (net (code "95") (name "unconnected-(U1-DDBUS6-Pad58)") (class "Default")
      (node (ref "U1") (pin "58") (pinfunction "DDBUS6_58") (pintype "passive+no_connect"))
    )
    (net (code "96") (name "unconnected-(U1-DDBUS7-Pad59)") (class "Default")
      (node (ref "U1") (pin "59") (pinfunction "DDBUS7_59") (pintype "passive+no_connect"))
    )
    (net (code "97") (name "unconnected-(U1-PWREN#-Pad60)") (class "Default")
      (node (ref "U1") (pin "60") (pinfunction "PWREN#_60") (pintype "passive+no_connect"))
    )
    (net (code "98") (name "unconnected-(U1-SUSPEND#-Pad36)") (class "Default")
      (node (ref "U1") (pin "36") (pinfunction "SUSPEND#_36") (pintype "passive+no_connect"))
    )
  )
)
